# BMS.net
KiCad netlist of a schematic drawn in Altium Designer
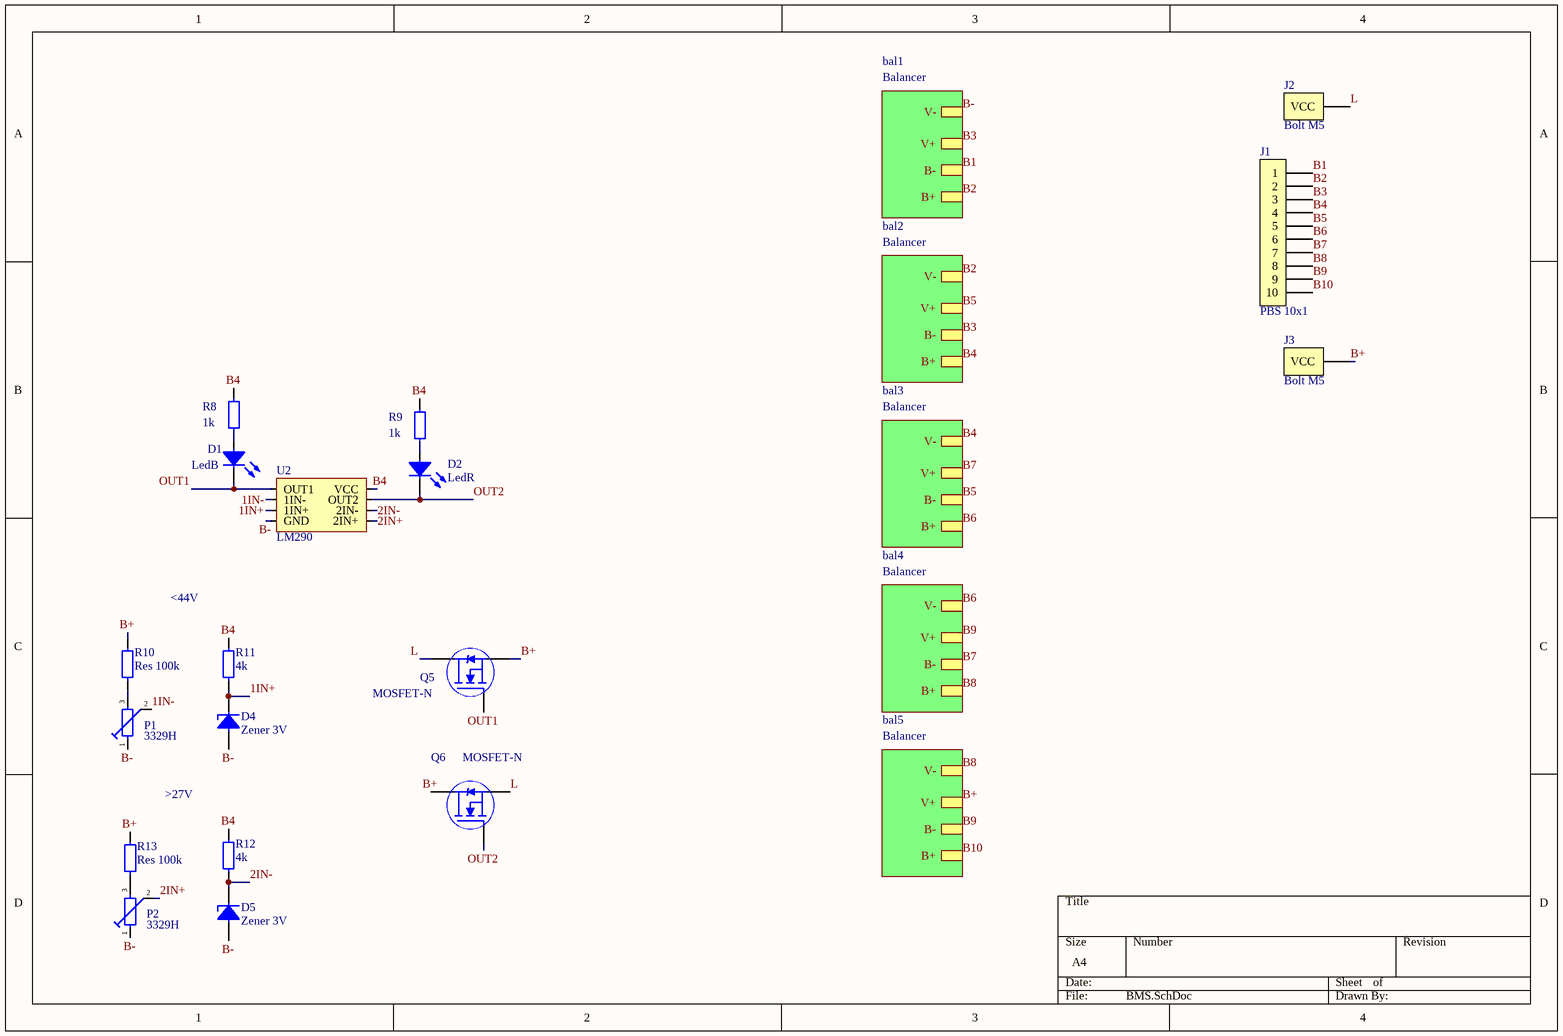
[diagram p0: BMS.SchDoc]

(export (version "E")
  (design (tool "Eeschema 10.0.6"))
  (components
    (comp (ref "D1")
      (value "LedB")
      (footprint "0805 LED")
      (description "SMD 1608, 247mcd, 120°, 592nM (High Bright Yellow)")
      (fields
        (field (name "PART NUMBER") "TO-1608BC-MYF")
        (field (name "MANUFACTURER") "Taiwan Oasis Technology")
      )
      (libsource (lib "BRT_Components") (part "Led Yellow"))
    )
    (comp (ref "D2")
      (value "LedR")
      (footprint "0805 LED")
      (description "SMD 1608, 112mcd, 120°, 630nM (Ultra Bright Red)")
      (fields
        (field (name "PART NUMBER") "TO-1608BC-MRE")
        (field (name "MANUFACTURER") "Taiwan Oasis Technology")
      )
      (libsource (lib "BRT_Components") (part "Led Red"))
    )
    (comp (ref "D4")
      (value "Zener 3V")
      (footprint "sod-123")
      (description "500mW")
      (fields
        (field (name "PART NUMBER") "MMSZ5225B")
        (field (name "MANUFACTURER") "Yangzhou Yangjie Electronic Technology")
      )
      (libsource (lib "BRT_Components") (part "Zener Diode 3V"))
    )
    (comp (ref "D5")
      (value "Zener 3V")
      (footprint "sod-123")
      (description "500mW")
      (fields
        (field (name "PART NUMBER") "MMSZ5225B")
        (field (name "MANUFACTURER") "Yangzhou Yangjie Electronic Technology")
      )
      (libsource (lib "BRT_Components") (part "Zener Diode 3V"))
    )
    (comp (ref "J1")
      (value "PBS 10x1")
      (footprint "PBS10")
      (description "Female")
      (fields
        (field (name "PART NUMBER") "DS1023-1*10S21")
        (field (name "MANUFACTURER") "Ningbo connfly electronic")
      )
      (libsource (lib "BRT_Components") (part "Conn 10 (PBS)"))
    )
    (comp (ref "J2")
      (value "Bolt M5")
      (footprint "Bolt M5")
      (description "Bolt M5 high corrent connector")
      (libsource (lib "BRT_Components") (part "Conn Bolt M5"))
    )
    (comp (ref "J3")
      (value "Bolt M5")
      (footprint "Bolt M5")
      (description "Bolt M5 high corrent connector")
      (libsource (lib "BRT_Components") (part "Conn Bolt M5"))
    )
    (comp (ref "P1")
      (value "3329H")
      (footprint "3329H")
      (description "Potentiometr 15k 0.5W")
      (fields (field (name "PART NUMBER") "M64X203KB40") (field (name "MANUFACTURER") "Vishay"))
      (libsource (lib "Pot") (part "Pot 15k"))
    )
    (comp (ref "P2")
      (value "3329H")
      (footprint "3329H")
      (description "Potentiometr 15k 0.5W")
      (fields (field (name "PART NUMBER") "M64X203KB40") (field (name "MANUFACTURER") "Vishay"))
      (libsource (lib "Pot") (part "Pot 15k"))
    )
    (comp (ref "Q5")
      (value "MOSFET-N")
      (footprint "D-Pak (TO-252AA)")
      (description "Trans MOSFET N-CH Si 55V 89A 3-Pin(2+Tab) DPAK Tube")
      (fields
        (field (name "PART NUMBER") "IRLR3705ZTRPBF")
        (field (name "MANUFACTURER") "International Rectifier")
      )
      (libsource (lib "BRT_Components") (part "MOSFET-N [IRLR]"))
    )
    (comp (ref "Q6")
      (value "MOSFET-N")
      (footprint "D-Pak (TO-252AA)")
      (description "Trans MOSFET N-CH Si 55V 89A 3-Pin(2+Tab) DPAK Tube")
      (fields
        (field (name "PART NUMBER") "IRLR3705ZTRPBF")
        (field (name "MANUFACTURER") "International Rectifier")
      )
      (libsource (lib "BRT_Components") (part "MOSFET-N [IRLR]"))
    )
    (comp (ref "R8")
      (value "1k")
      (footprint "0805 Resistor")
      (description "0.125W 0805 3.9k, 1%")
      (fields (field (name "PART NUMBER") "RC0805FR-073K9L") (field (name "MANUFACTURER") "Taiwan"))
      (libsource (lib "BRT_Components") (part "Res 3.9k (0805)"))
    )
    (comp (ref "R9")
      (value "1k")
      (footprint "0805 Resistor")
      (description "0.125W 0805 3.9k, 1%")
      (fields (field (name "PART NUMBER") "RC0805FR-073K9L") (field (name "MANUFACTURER") "Taiwan"))
      (libsource (lib "BRT_Components") (part "Res 3.9k (0805)"))
    )
    (comp (ref "R10")
      (value "Res 100k")
      (footprint "0805 Resistor")
      (description "0.125W 0805 100k, 1%")
      (fields (field (name "PART NUMBER") "RC0805FR-07100KL") (field (name "MANUFACTURER") "Taiwan"))
      (libsource (lib "BRT_Components") (part "Res 100k (0805)"))
    )
    (comp (ref "R11")
      (value "4k")
      (footprint "0805 Resistor")
      (description "0.125W 0805 6.8k, 1%")
      (fields (field (name "PART NUMBER") "RC0805FR-076K8L") (field (name "MANUFACTURER") "Taiwan"))
      (libsource (lib "BRT_Components") (part "Res 6.8k (0805)"))
    )
    (comp (ref "R12")
      (value "4k")
      (footprint "0805 Resistor")
      (description "0.125W 0805 6.8k, 1%")
      (fields (field (name "PART NUMBER") "RC0805FR-076K8L") (field (name "MANUFACTURER") "Taiwan"))
      (libsource (lib "BRT_Components") (part "Res 6.8k (0805)"))
    )
    (comp (ref "R13")
      (value "Res 100k")
      (footprint "0805 Resistor")
      (description "0.125W 0805 100k, 1%")
      (fields (field (name "PART NUMBER") "RC0805FR-07100KL") (field (name "MANUFACTURER") "Taiwan"))
      (libsource (lib "BRT_Components") (part "Res 100k (0805)"))
    )
    (comp (ref "U2")
      (value "LM290")
      (footprint "SOIC-8")
      (description "LM290 SOIC-8")
      (libsource (lib "LM290") (part "Comp 2x"))
    )
  )
  (nets
    (net (code "1") (name "/1IN+") (class "Default")
      (node (ref "D4") (pin "2") (pinfunction "2_2") (pintype "passive"))
      (node (ref "R11") (pin "1") (pinfunction "1_1") (pintype "passive"))
      (node (ref "U2") (pin "3") (pinfunction "1IN+_3") (pintype "passive"))
    )
    (net (code "2") (name "/1IN-") (class "Default")
      (node (ref "P1") (pin "2") (pinfunction "2_2") (pintype "passive"))
      (node (ref "U2") (pin "2") (pinfunction "1IN-_2") (pintype "passive"))
    )
    (net (code "3") (name "/2IN+") (class "Default")
      (node (ref "P2") (pin "2") (pinfunction "2_2") (pintype "passive"))
      (node (ref "U2") (pin "5") (pinfunction "2IN+_5") (pintype "passive"))
    )
    (net (code "4") (name "/2IN-") (class "Default")
      (node (ref "D5") (pin "2") (pinfunction "2_2") (pintype "passive"))
      (node (ref "R12") (pin "1") (pinfunction "1_1") (pintype "passive"))
      (node (ref "U2") (pin "6") (pinfunction "2IN-_6") (pintype "passive"))
    )
    (net (code "5") (name "/B+") (class "Default")
      (node (ref "J3") (pin "1") (pinfunction "VCC_1") (pintype "passive"))
      (node (ref "Q5") (pin "3") (pinfunction "Source_3") (pintype "passive"))
      (node (ref "Q6") (pin "2") (pinfunction "Drain_2") (pintype "passive"))
      (node (ref "R10") (pin "2") (pinfunction "2_2") (pintype "passive"))
      (node (ref "R13") (pin "2") (pinfunction "2_2") (pintype "passive"))
    )
    (net (code "6") (name "/B-") (class "Default")
      (node (ref "D4") (pin "1") (pinfunction "1_1") (pintype "passive"))
      (node (ref "D5") (pin "1") (pinfunction "1_1") (pintype "passive"))
      (node (ref "P1") (pin "1") (pinfunction "1_1") (pintype "passive"))
      (node (ref "P2") (pin "1") (pinfunction "1_1") (pintype "passive"))
      (node (ref "U2") (pin "4") (pinfunction "GND_4") (pintype "passive"))
    )
    (net (code "7") (name "/B1") (class "Default")
      (node (ref "J1") (pin "1") (pinfunction "1_1") (pintype "passive"))
    )
    (net (code "8") (name "/B2") (class "Default")
      (node (ref "J1") (pin "2") (pinfunction "2_2") (pintype "passive"))
    )
    (net (code "9") (name "/B3") (class "Default")
      (node (ref "J1") (pin "3") (pinfunction "3_3") (pintype "passive"))
    )
    (net (code "10") (name "/B4") (class "Default")
      (node (ref "J1") (pin "4") (pinfunction "4_4") (pintype "passive"))
      (node (ref "R11") (pin "2") (pinfunction "2_2") (pintype "passive"))
      (node (ref "R12") (pin "2") (pinfunction "2_2") (pintype "passive"))
      (node (ref "R8") (pin "2") (pinfunction "2_2") (pintype "passive"))
      (node (ref "R9") (pin "2") (pinfunction "2_2") (pintype "passive"))
      (node (ref "U2") (pin "8") (pinfunction "VCC_8") (pintype "passive"))
    )
    (net (code "11") (name "/B5") (class "Default")
      (node (ref "J1") (pin "5") (pinfunction "5_5") (pintype "passive"))
    )
    (net (code "12") (name "/B6") (class "Default")
      (node (ref "J1") (pin "6") (pinfunction "6_6") (pintype "passive"))
    )
    (net (code "13") (name "/B7") (class "Default")
      (node (ref "J1") (pin "7") (pinfunction "7_7") (pintype "passive"))
    )
    (net (code "14") (name "/B8") (class "Default")
      (node (ref "J1") (pin "8") (pinfunction "8_8") (pintype "passive"))
    )
    (net (code "15") (name "/B9") (class "Default")
      (node (ref "J1") (pin "9") (pinfunction "9_9") (pintype "passive"))
    )
    (net (code "16") (name "/B10") (class "Default")
      (node (ref "J1") (pin "10") (pinfunction "10_10") (pintype "passive"))
    )
    (net (code "17") (name "/L") (class "Default")
      (node (ref "J2") (pin "1") (pinfunction "VCC_1") (pintype "passive"))
      (node (ref "Q5") (pin "2") (pinfunction "Drain_2") (pintype "passive"))
      (node (ref "Q6") (pin "3") (pinfunction "Source_3") (pintype "passive"))
    )
    (net (code "18") (name "/OUT1") (class "Default")
      (node (ref "D1") (pin "2") (pinfunction "2_2") (pintype "passive"))
      (node (ref "Q5") (pin "1") (pinfunction "Gate_1") (pintype "passive"))
      (node (ref "U2") (pin "1") (pinfunction "OUT1_1") (pintype "passive"))
    )
    (net (code "19") (name "/OUT2") (class "Default")
      (node (ref "D2") (pin "2") (pinfunction "2_2") (pintype "passive"))
      (node (ref "Q6") (pin "1") (pinfunction "Gate_1") (pintype "passive"))
      (node (ref "U2") (pin "7") (pinfunction "OUT2_7") (pintype "passive"))
    )
    (net (code "20") (name "Net-(D1-Pad1)") (class "Default")
      (node (ref "D1") (pin "1") (pinfunction "1_1") (pintype "passive"))
      (node (ref "R8") (pin "1") (pinfunction "1_1") (pintype "passive"))
    )
    (net (code "21") (name "Net-(D2-Pad1)") (class "Default")
      (node (ref "D2") (pin "1") (pinfunction "1_1") (pintype "passive"))
      (node (ref "R9") (pin "1") (pinfunction "1_1") (pintype "passive"))
    )
    (net (code "22") (name "Net-(P1-Pad3)") (class "Default")
      (node (ref "P1") (pin "3") (pinfunction "3_3") (pintype "passive"))
      (node (ref "R10") (pin "1") (pinfunction "1_1") (pintype "passive"))
    )
    (net (code "23") (name "Net-(P2-Pad3)") (class "Default")
      (node (ref "P2") (pin "3") (pinfunction "3_3") (pintype "passive"))
      (node (ref "R13") (pin "1") (pinfunction "1_1") (pintype "passive"))
    )
  )
)
